# Sensor_Board_Schematic.net
KiCad netlist of a schematic drawn in EAGLE
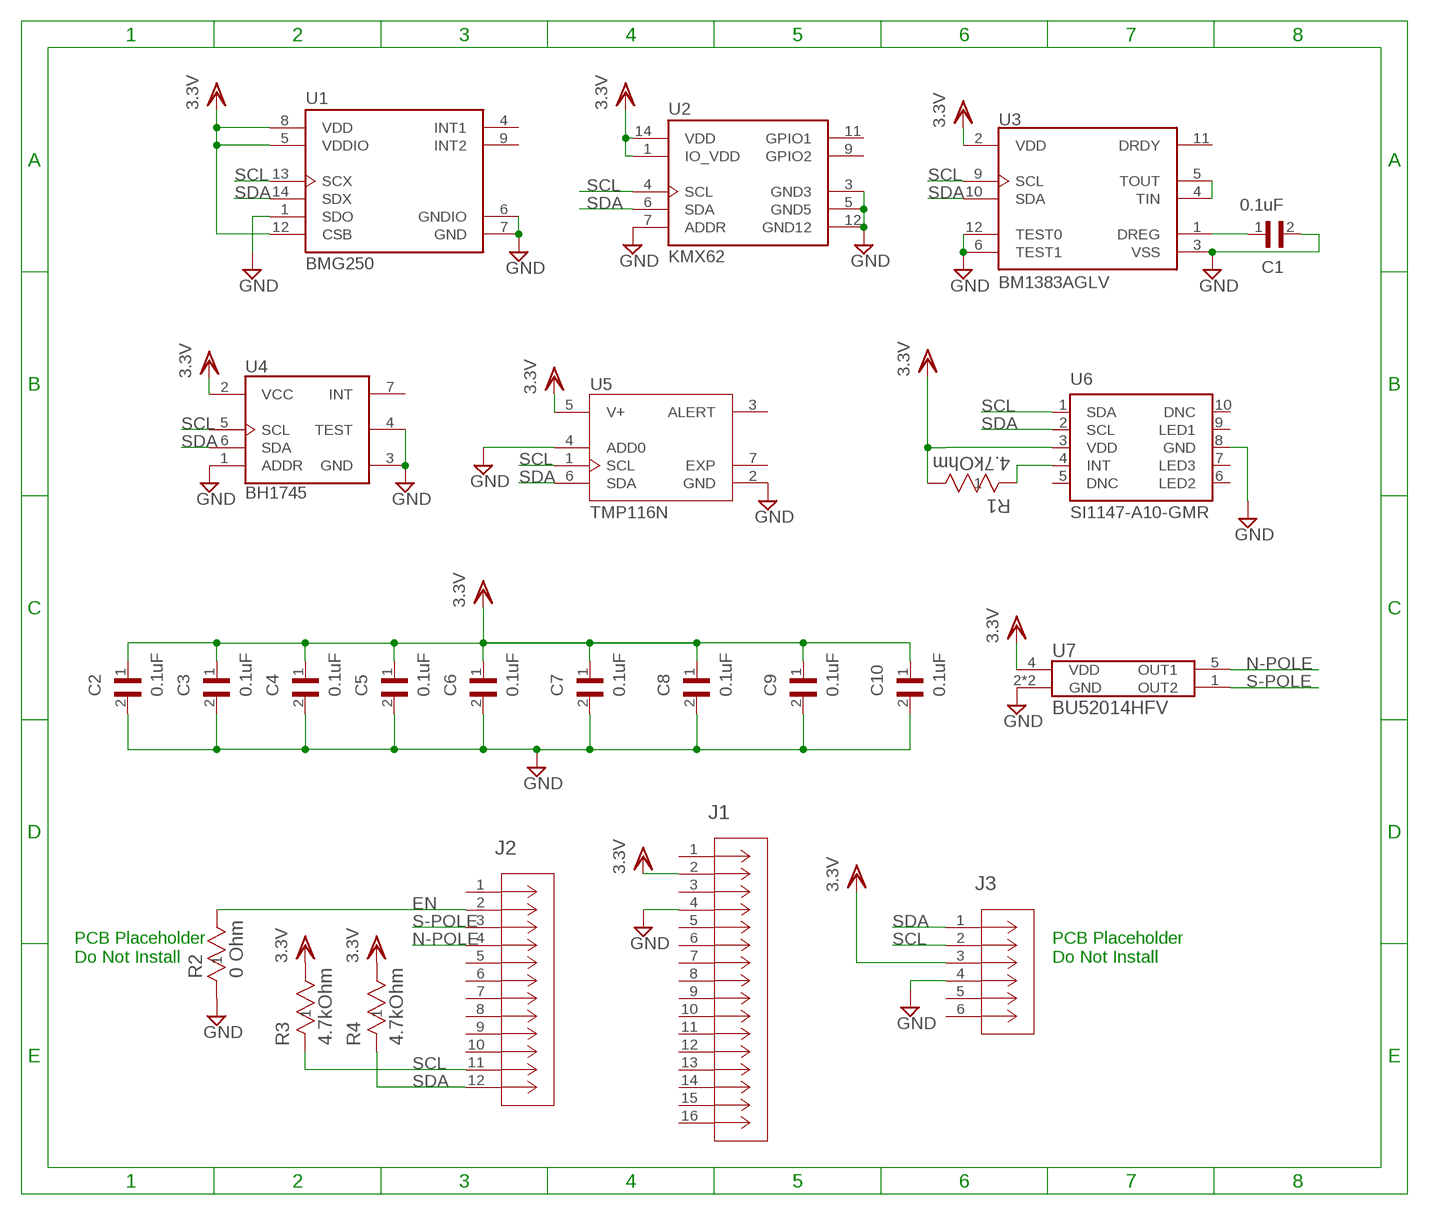
[diagram p0: schematic, sheet 1]

(export (version "E")
  (design (tool "Eeschema 10.0.6"))
  (components
    (comp (ref "C1")
      (value "0.1uF")
      (footprint "eagle-import:CAPC0603X33N")
      (fields
        (field (name "DIGI-KEY_PART_NUMBER") "490-10390-1-ND")
        (field (name "MF") "Murata Electronics")
        (field (name "MP") "GRM033C80J104KE15D")
      )
      (libsource (lib "eagle-import") (part "GRM033C80J104KE15D"))
    )
    (comp (ref "C2")
      (value "0.1uF")
      (footprint "eagle-import:CAPC0603X33N")
      (fields
        (field (name "DIGI-KEY_PART_NUMBER") "490-10390-1-ND")
        (field (name "MF") "Murata Electronics")
        (field (name "MP") "GRM033C80J104KE15D")
      )
      (libsource (lib "eagle-import") (part "GRM033C80J104KE15D"))
    )
    (comp (ref "C3")
      (value "0.1uF")
      (footprint "eagle-import:CAPC0603X33N")
      (fields
        (field (name "DIGI-KEY_PART_NUMBER") "490-10390-1-ND")
        (field (name "MF") "Murata Electronics")
        (field (name "MP") "GRM033C80J104KE15D")
      )
      (libsource (lib "eagle-import") (part "GRM033C80J104KE15D"))
    )
    (comp (ref "C4")
      (value "0.1uF")
      (footprint "eagle-import:CAPC0603X33N")
      (fields
        (field (name "DIGI-KEY_PART_NUMBER") "490-10390-1-ND")
        (field (name "MF") "Murata Electronics")
        (field (name "MP") "GRM033C80J104KE15D")
      )
      (libsource (lib "eagle-import") (part "GRM033C80J104KE15D"))
    )
    (comp (ref "C5")
      (value "0.1uF")
      (footprint "eagle-import:CAPC0603X33N")
      (fields
        (field (name "DIGI-KEY_PART_NUMBER") "490-10390-1-ND")
        (field (name "MF") "Murata Electronics")
        (field (name "MP") "GRM033C80J104KE15D")
      )
      (libsource (lib "eagle-import") (part "GRM033C80J104KE15D"))
    )
    (comp (ref "C6")
      (value "0.1uF")
      (footprint "eagle-import:CAPC0603X33N")
      (fields
        (field (name "DIGI-KEY_PART_NUMBER") "490-10390-1-ND")
        (field (name "MF") "Murata Electronics")
        (field (name "MP") "GRM033C80J104KE15D")
      )
      (libsource (lib "eagle-import") (part "GRM033C80J104KE15D"))
    )
    (comp (ref "C7")
      (value "0.1uF")
      (footprint "eagle-import:CAPC0603X33N")
      (fields
        (field (name "DIGI-KEY_PART_NUMBER") "490-10390-1-ND")
        (field (name "MF") "Murata Electronics")
        (field (name "MP") "GRM033C80J104KE15D")
      )
      (libsource (lib "eagle-import") (part "GRM033C80J104KE15D"))
    )
    (comp (ref "C8")
      (value "0.1uF")
      (footprint "eagle-import:CAPC0603X33N")
      (fields
        (field (name "DIGI-KEY_PART_NUMBER") "490-10390-1-ND")
        (field (name "MF") "Murata Electronics")
        (field (name "MP") "GRM033C80J104KE15D")
      )
      (libsource (lib "eagle-import") (part "GRM033C80J104KE15D"))
    )
    (comp (ref "C9")
      (value "0.1uF")
      (footprint "eagle-import:CAPC0603X33N")
      (fields
        (field (name "DIGI-KEY_PART_NUMBER") "490-10390-1-ND")
        (field (name "MF") "Murata Electronics")
        (field (name "MP") "GRM033C80J104KE15D")
      )
      (libsource (lib "eagle-import") (part "GRM033C80J104KE15D"))
    )
    (comp (ref "C10")
      (value "0.1uF")
      (footprint "eagle-import:CAPC0603X33N")
      (fields
        (field (name "DIGI-KEY_PART_NUMBER") "490-10390-1-ND")
        (field (name "MF") "Murata Electronics")
        (field (name "MP") "GRM033C80J104KE15D")
      )
      (libsource (lib "eagle-import") (part "GRM033C80J104KE15D"))
    )
    (comp (ref "J1")
      (value "SSQ-116-03-T-S")
      (footprint "eagle-import:CON16_1X16_TU_SSQ")
      (fields (field (name "MANUFACTURER_PART_NUMBER") "SSQ11603TS"))
      (libsource (lib "eagle-import") (part "SSQ-116-03-T-S"))
    )
    (comp (ref "J2")
      (value "SSQ-112-03-T-S")
      (footprint "eagle-import:CON12_1X12_TU_SSQ")
      (fields (field (name "MANUFACTURER_PART_NUMBER") "SSQ11203TS"))
      (libsource (lib "eagle-import") (part "SSQ-112-03-T-S"))
    )
    (comp (ref "J3")
      (value "SSQ-106-03-T-S")
      (footprint "eagle-import:CON6_1X6_TU_SSQ")
      (fields (field (name "MANUFACTURER_PART_NUMBER") "SSQ10603TS"))
      (libsource (lib "eagle-import") (part "SSQ-106-03-T-S"))
    )
    (comp (ref "R1")
      (value "4.7kOhm")
      (footprint "eagle-import:STA_RMCF0402")
      (fields (field (name "MANUFACTURER_PART_NUMBER") "RMCF0402JT4K70"))
      (libsource (lib "eagle-import") (part "RMCF0402JT4K70"))
    )
    (comp (ref "R2")
      (value "0 Ohm")
      (footprint "eagle-import:STA_RMCF0402")
      (fields (field (name "MANUFACTURER_PART_NUMBER") "RMCF0402ZT0R00"))
      (libsource (lib "eagle-import") (part "RMCF0402ZT0R00"))
    )
    (comp (ref "R3")
      (value "4.7kOhm")
      (footprint "eagle-import:STA_RMCF0402")
      (fields (field (name "MANUFACTURER_PART_NUMBER") "RMCF0402JT4K70"))
      (libsource (lib "eagle-import") (part "RMCF0402JT4K70"))
    )
    (comp (ref "R4")
      (value "4.7kOhm")
      (footprint "eagle-import:STA_RMCF0402")
      (fields (field (name "MANUFACTURER_PART_NUMBER") "RMCF0402JT4K70"))
      (libsource (lib "eagle-import") (part "RMCF0402JT4K70"))
    )
    (comp (ref "U1")
      (value "BMG250")
      (footprint "eagle-import:BMG250FP")
      (libsource (lib "eagle-import") (part "BMG250"))
    )
    (comp (ref "U2")
      (value "KMX62")
      (footprint "eagle-import:LGA-16-3X2.5")
      (libsource (lib "eagle-import") (part "KMX62"))
    )
    (comp (ref "U3")
      (value "BM1383AGLV-ZE2")
      (footprint "eagle-import:PQFN55P250X250X100-12N")
      (fields (field (name "DIGI-KEY_PART_NUMBER") "BM1383AGLV-ZE2CT-ND") (field (name "MF") "Rohm"))
      (libsource (lib "eagle-import") (part "BM1383AGLV-ZE2"))
    )
    (comp (ref "U4")
      (value "BH1745")
      (footprint "eagle-import:BH1745")
      (libsource (lib "eagle-import") (part "BH1745"))
    )
    (comp (ref "U5")
      (value "TMP116NAIDRVR")
      (footprint "eagle-import:SON65P200X200X80-7N")
      (fields (field (name "DIGI-KEY_PART_NUMBER") "296-48306-1-ND") (field (name "MF") "Texas Instruments"))
      (libsource (lib "eagle-import") (part "TMP116NAIDRVR"))
    )
    (comp (ref "U6")
      (value "SI1147-A10-GMR")
      (footprint "eagle-import:QFN10-2X2")
      (fields (field (name "MF") "Silicon Labs") (field (name "MPN") "Si1147-A10-GMR"))
      (libsource (lib "eagle-import") (part "SI1147-A10-GMR"))
    )
    (comp (ref "U7")
      (value "BU52014HFV")
      (footprint "eagle-import:SOP50P160X60-5N")
      (fields
        (field (name "DIGI-KEY_PART_NUMBER") "BU52014HFVCT-ND")
        (field (name "MF") "Rohm")
        (field (name "MP") "BU52014HFV-TR")
      )
      (libsource (lib "eagle-import") (part "BU52014HFV"))
    )
  )
  (nets
    (net (code "1") (name "/EN") (class "Default")
      (node (ref "J2") (pin "2") (pinfunction "2_2") (pintype "passive"))
      (node (ref "R2") (pin "2") (pinfunction "2_2") (pintype "passive"))
    )
    (net (code "2") (name "/EXP") (class "Default")
      (node (ref "U5") (pin "7") (pinfunction "EXP_7") (pintype "power_in"))
    )
    (net (code "3") (name "/N-POLE") (class "Default")
      (node (ref "J2") (pin "4") (pinfunction "4_4") (pintype "passive"))
      (node (ref "U7") (pin "5") (pinfunction "OUT1_5") (pintype "output"))
    )
    (net (code "4") (name "/S-POLE") (class "Default")
      (node (ref "J2") (pin "3") (pinfunction "3_3") (pintype "passive"))
      (node (ref "U7") (pin "1") (pinfunction "OUT2_1") (pintype "output"))
    )
    (net (code "5") (name "/SCL") (class "Default")
      (node (ref "J2") (pin "11") (pinfunction "11_11") (pintype "passive"))
      (node (ref "J3") (pin "2") (pinfunction "2_2") (pintype "passive"))
      (node (ref "R3") (pin "1") (pinfunction "1_1") (pintype "passive"))
      (node (ref "U1") (pin "13") (pinfunction "SCX_13") (pintype "input"))
      (node (ref "U2") (pin "4") (pinfunction "SCL_4") (pintype "input"))
      (node (ref "U3") (pin "9") (pinfunction "SCL_9") (pintype "input"))
      (node (ref "U4") (pin "5") (pinfunction "SCL_5") (pintype "input"))
      (node (ref "U5") (pin "1") (pinfunction "SCL_1") (pintype "input"))
      (node (ref "U6") (pin "1") (pinfunction "SDA_1") (pintype "bidirectional"))
    )
    (net (code "6") (name "/SDA") (class "Default")
      (node (ref "J2") (pin "12") (pinfunction "12_12") (pintype "passive"))
      (node (ref "J3") (pin "1") (pinfunction "1_1") (pintype "passive"))
      (node (ref "R4") (pin "1") (pinfunction "1_1") (pintype "passive"))
      (node (ref "U1") (pin "14") (pinfunction "SDX_14") (pintype "bidirectional"))
      (node (ref "U2") (pin "6") (pinfunction "SDA_6") (pintype "bidirectional"))
      (node (ref "U3") (pin "10") (pinfunction "SDA_10") (pintype "bidirectional"))
      (node (ref "U4") (pin "6") (pinfunction "SDA_6") (pintype "bidirectional"))
      (node (ref "U5") (pin "6") (pinfunction "SDA_6") (pintype "bidirectional"))
      (node (ref "U6") (pin "2") (pinfunction "SCL_2") (pintype "input"))
    )
    (net (code "7") (name "3.3V") (class "Default")
      (node (ref "C10") (pin "1") (pinfunction "1_1") (pintype "passive"))
      (node (ref "C2") (pin "1") (pinfunction "1_1") (pintype "passive"))
      (node (ref "C3") (pin "1") (pinfunction "1_1") (pintype "passive"))
      (node (ref "C4") (pin "1") (pinfunction "1_1") (pintype "passive"))
      (node (ref "C5") (pin "1") (pinfunction "1_1") (pintype "passive"))
      (node (ref "C6") (pin "1") (pinfunction "1_1") (pintype "passive"))
      (node (ref "C7") (pin "1") (pinfunction "1_1") (pintype "passive"))
      (node (ref "C8") (pin "1") (pinfunction "1_1") (pintype "passive"))
      (node (ref "C9") (pin "1") (pinfunction "1_1") (pintype "passive"))
      (node (ref "J1") (pin "2") (pinfunction "2_2") (pintype "passive"))
      (node (ref "J3") (pin "3") (pinfunction "3_3") (pintype "passive"))
      (node (ref "R1") (pin "2") (pinfunction "2_2") (pintype "passive"))
      (node (ref "R3") (pin "2") (pinfunction "2_2") (pintype "passive"))
      (node (ref "R4") (pin "2") (pinfunction "2_2") (pintype "passive"))
      (node (ref "U1") (pin "12") (pinfunction "CSB_12") (pintype "input"))
      (node (ref "U1") (pin "5") (pinfunction "VDDIO_5") (pintype "power_in"))
      (node (ref "U1") (pin "8") (pinfunction "VDD_8") (pintype "power_in"))
      (node (ref "U2") (pin "1") (pinfunction "IO_VDD_1") (pintype "power_in"))
      (node (ref "U2") (pin "14") (pinfunction "VDD_14") (pintype "power_in"))
      (node (ref "U3") (pin "2") (pinfunction "VDD_2") (pintype "power_in"))
      (node (ref "U4") (pin "2") (pinfunction "VCC_2") (pintype "power_in"))
      (node (ref "U5") (pin "5") (pinfunction "V+_5") (pintype "power_in"))
      (node (ref "U6") (pin "3") (pinfunction "VDD_3") (pintype "power_in"))
      (node (ref "U7") (pin "4") (pinfunction "VDD_4") (pintype "power_in"))
    )
    (net (code "8") (name "GND") (class "Default")
      (node (ref "C1") (pin "2") (pinfunction "2_2") (pintype "passive"))
      (node (ref "C10") (pin "2") (pinfunction "2_2") (pintype "passive"))
      (node (ref "C2") (pin "2") (pinfunction "2_2") (pintype "passive"))
      (node (ref "C3") (pin "2") (pinfunction "2_2") (pintype "passive"))
      (node (ref "C4") (pin "2") (pinfunction "2_2") (pintype "passive"))
      (node (ref "C5") (pin "2") (pinfunction "2_2") (pintype "passive"))
      (node (ref "C6") (pin "2") (pinfunction "2_2") (pintype "passive"))
      (node (ref "C7") (pin "2") (pinfunction "2_2") (pintype "passive"))
      (node (ref "C8") (pin "2") (pinfunction "2_2") (pintype "passive"))
      (node (ref "C9") (pin "2") (pinfunction "2_2") (pintype "passive"))
      (node (ref "J1") (pin "4") (pinfunction "4_4") (pintype "passive"))
      (node (ref "J3") (pin "4") (pinfunction "4_4") (pintype "passive"))
      (node (ref "R2") (pin "1") (pinfunction "1_1") (pintype "passive"))
      (node (ref "U1") (pin "1") (pinfunction "SDO_1") (pintype "bidirectional"))
      (node (ref "U1") (pin "6") (pinfunction "GNDIO_6") (pintype "power_in"))
      (node (ref "U1") (pin "7") (pinfunction "GND_7") (pintype "power_in"))
      (node (ref "U2") (pin "12") (pinfunction "GND12_12") (pintype "power_in"))
      (node (ref "U2") (pin "3") (pinfunction "GND3_3") (pintype "power_in"))
      (node (ref "U2") (pin "5") (pinfunction "GND5_5") (pintype "power_in"))
      (node (ref "U2") (pin "7") (pinfunction "ADDR_7") (pintype "input"))
      (node (ref "U3") (pin "12") (pinfunction "TEST0_12") (pintype "input"))
      (node (ref "U3") (pin "3") (pinfunction "VSS_3") (pintype "power_in"))
      (node (ref "U3") (pin "6") (pinfunction "TEST1_6") (pintype "input"))
      (node (ref "U4") (pin "1") (pinfunction "ADDR_1") (pintype "input"))
      (node (ref "U4") (pin "3") (pinfunction "GND_3") (pintype "power_in"))
      (node (ref "U4") (pin "4") (pinfunction "TEST_4") (pintype "bidirectional"))
      (node (ref "U5") (pin "2") (pinfunction "GND_2") (pintype "power_in"))
      (node (ref "U5") (pin "4") (pinfunction "ADD0_4") (pintype "input"))
      (node (ref "U6") (pin "8") (pinfunction "GND_8") (pintype "power_in"))
      (node (ref "U7") (pin "2") (pinfunction "GND_2") (pintype "power_in"))
      (node (ref "U7") (pin "2.2") (pinfunction "GND_2.2") (pintype "power_in"))
    )
    (net (code "9") (name "Net-(U3-DREG)") (class "Default")
      (node (ref "C1") (pin "1") (pinfunction "1_1") (pintype "passive"))
      (node (ref "U3") (pin "1") (pinfunction "DREG_1") (pintype "passive"))
    )
    (net (code "10") (name "Net-(U3-TIN)") (class "Default")
      (node (ref "U3") (pin "4") (pinfunction "TIN_4") (pintype "input"))
      (node (ref "U3") (pin "5") (pinfunction "TOUT_5") (pintype "output"))
    )
    (net (code "11") (name "Net-(U6-INT)") (class "Default")
      (node (ref "R1") (pin "1") (pinfunction "1_1") (pintype "passive"))
      (node (ref "U6") (pin "4") (pinfunction "INT_4") (pintype "bidirectional"))
    )
    (net (code "12") (name "unconnected-(J1-Pad1)") (class "Default")
      (node (ref "J1") (pin "1") (pinfunction "1_1") (pintype "passive"))
    )
    (net (code "13") (name "unconnected-(J1-Pad3)") (class "Default")
      (node (ref "J1") (pin "3") (pinfunction "3_3") (pintype "passive"))
    )
    (net (code "14") (name "unconnected-(J1-Pad5)") (class "Default")
      (node (ref "J1") (pin "5") (pinfunction "5_5") (pintype "passive"))
    )
    (net (code "15") (name "unconnected-(J1-Pad6)") (class "Default")
      (node (ref "J1") (pin "6") (pinfunction "6_6") (pintype "passive"))
    )
    (net (code "16") (name "unconnected-(J1-Pad7)") (class "Default")
      (node (ref "J1") (pin "7") (pinfunction "7_7") (pintype "passive"))
    )
    (net (code "17") (name "unconnected-(J1-Pad8)") (class "Default")
      (node (ref "J1") (pin "8") (pinfunction "8_8") (pintype "passive"))
    )
    (net (code "18") (name "unconnected-(J1-Pad9)") (class "Default")
      (node (ref "J1") (pin "9") (pinfunction "9_9") (pintype "passive"))
    )
    (net (code "19") (name "unconnected-(J1-Pad10)") (class "Default")
      (node (ref "J1") (pin "10") (pinfunction "10_10") (pintype "passive"))
    )
    (net (code "20") (name "unconnected-(J1-Pad11)") (class "Default")
      (node (ref "J1") (pin "11") (pinfunction "11_11") (pintype "passive"))
    )
    (net (code "21") (name "unconnected-(J1-Pad12)") (class "Default")
      (node (ref "J1") (pin "12") (pinfunction "12_12") (pintype "passive"))
    )
    (net (code "22") (name "unconnected-(J1-Pad13)") (class "Default")
      (node (ref "J1") (pin "13") (pinfunction "13_13") (pintype "passive"))
    )
    (net (code "23") (name "unconnected-(J1-Pad14)") (class "Default")
      (node (ref "J1") (pin "14") (pinfunction "14_14") (pintype "passive"))
    )
    (net (code "24") (name "unconnected-(J1-Pad15)") (class "Default")
      (node (ref "J1") (pin "15") (pinfunction "15_15") (pintype "passive"))
    )
    (net (code "25") (name "unconnected-(J1-Pad16)") (class "Default")
      (node (ref "J1") (pin "16") (pinfunction "16_16") (pintype "passive"))
    )
    (net (code "26") (name "unconnected-(J2-Pad1)") (class "Default")
      (node (ref "J2") (pin "1") (pinfunction "1_1") (pintype "passive"))
    )
    (net (code "27") (name "unconnected-(J2-Pad5)") (class "Default")
      (node (ref "J2") (pin "5") (pinfunction "5_5") (pintype "passive"))
    )
    (net (code "28") (name "unconnected-(J2-Pad6)") (class "Default")
      (node (ref "J2") (pin "6") (pinfunction "6_6") (pintype "passive"))
    )
    (net (code "29") (name "unconnected-(J2-Pad7)") (class "Default")
      (node (ref "J2") (pin "7") (pinfunction "7_7") (pintype "passive"))
    )
    (net (code "30") (name "unconnected-(J2-Pad8)") (class "Default")
      (node (ref "J2") (pin "8") (pinfunction "8_8") (pintype "passive"))
    )
    (net (code "31") (name "unconnected-(J2-Pad9)") (class "Default")
      (node (ref "J2") (pin "9") (pinfunction "9_9") (pintype "passive"))
    )
    (net (code "32") (name "unconnected-(J2-Pad10)") (class "Default")
      (node (ref "J2") (pin "10") (pinfunction "10_10") (pintype "passive"))
    )
    (net (code "33") (name "unconnected-(J3-Pad5)") (class "Default")
      (node (ref "J3") (pin "5") (pinfunction "5_5") (pintype "passive"))
    )
    (net (code "34") (name "unconnected-(J3-Pad6)") (class "Default")
      (node (ref "J3") (pin "6") (pinfunction "6_6") (pintype "passive"))
    )
    (net (code "35") (name "unconnected-(U1-INT1-Pad4)") (class "Default")
      (node (ref "U1") (pin "4") (pinfunction "INT1_4") (pintype "bidirectional"))
    )
    (net (code "36") (name "unconnected-(U1-INT2-Pad9)") (class "Default")
      (node (ref "U1") (pin "9") (pinfunction "INT2_9") (pintype "bidirectional"))
    )
    (net (code "37") (name "unconnected-(U2-GPIO1-Pad11)") (class "Default")
      (node (ref "U2") (pin "11") (pinfunction "GPIO1_11") (pintype "bidirectional"))
    )
    (net (code "38") (name "unconnected-(U2-GPIO2-Pad9)") (class "Default")
      (node (ref "U2") (pin "9") (pinfunction "GPIO2_9") (pintype "bidirectional"))
    )
    (net (code "39") (name "unconnected-(U3-DRDY-Pad11)") (class "Default")
      (node (ref "U3") (pin "11") (pinfunction "DRDY_11") (pintype "output"))
    )
    (net (code "40") (name "unconnected-(U4-INT-Pad7)") (class "Default")
      (node (ref "U4") (pin "7") (pinfunction "INT_7") (pintype "no_connect"))
    )
    (net (code "41") (name "unconnected-(U5-ALERT-Pad3)") (class "Default")
      (node (ref "U5") (pin "3") (pinfunction "ALERT_3") (pintype "output"))
    )
    (net (code "42") (name "unconnected-(U6-DNC-Pad5)") (class "Default")
      (node (ref "U6") (pin "5") (pinfunction "DNC_5") (pintype "no_connect"))
    )
    (net (code "43") (name "unconnected-(U6-DNC-Pad10)") (class "Default")
      (node (ref "U6") (pin "10") (pinfunction "DNC_10") (pintype "no_connect"))
    )
    (net (code "44") (name "unconnected-(U6-LED1-Pad9)") (class "Default")
      (node (ref "U6") (pin "9") (pinfunction "LED1_9") (pintype "output"))
    )
    (net (code "45") (name "unconnected-(U6-LED2-Pad6)") (class "Default")
      (node (ref "U6") (pin "6") (pinfunction "LED2_6") (pintype "output"))
    )
    (net (code "46") (name "unconnected-(U6-LED3-Pad7)") (class "Default")
      (node (ref "U6") (pin "7") (pinfunction "LED3_7") (pintype "output"))
    )
  )
)
